# main.net
KiCad netlist of a schematic drawn in EAGLE
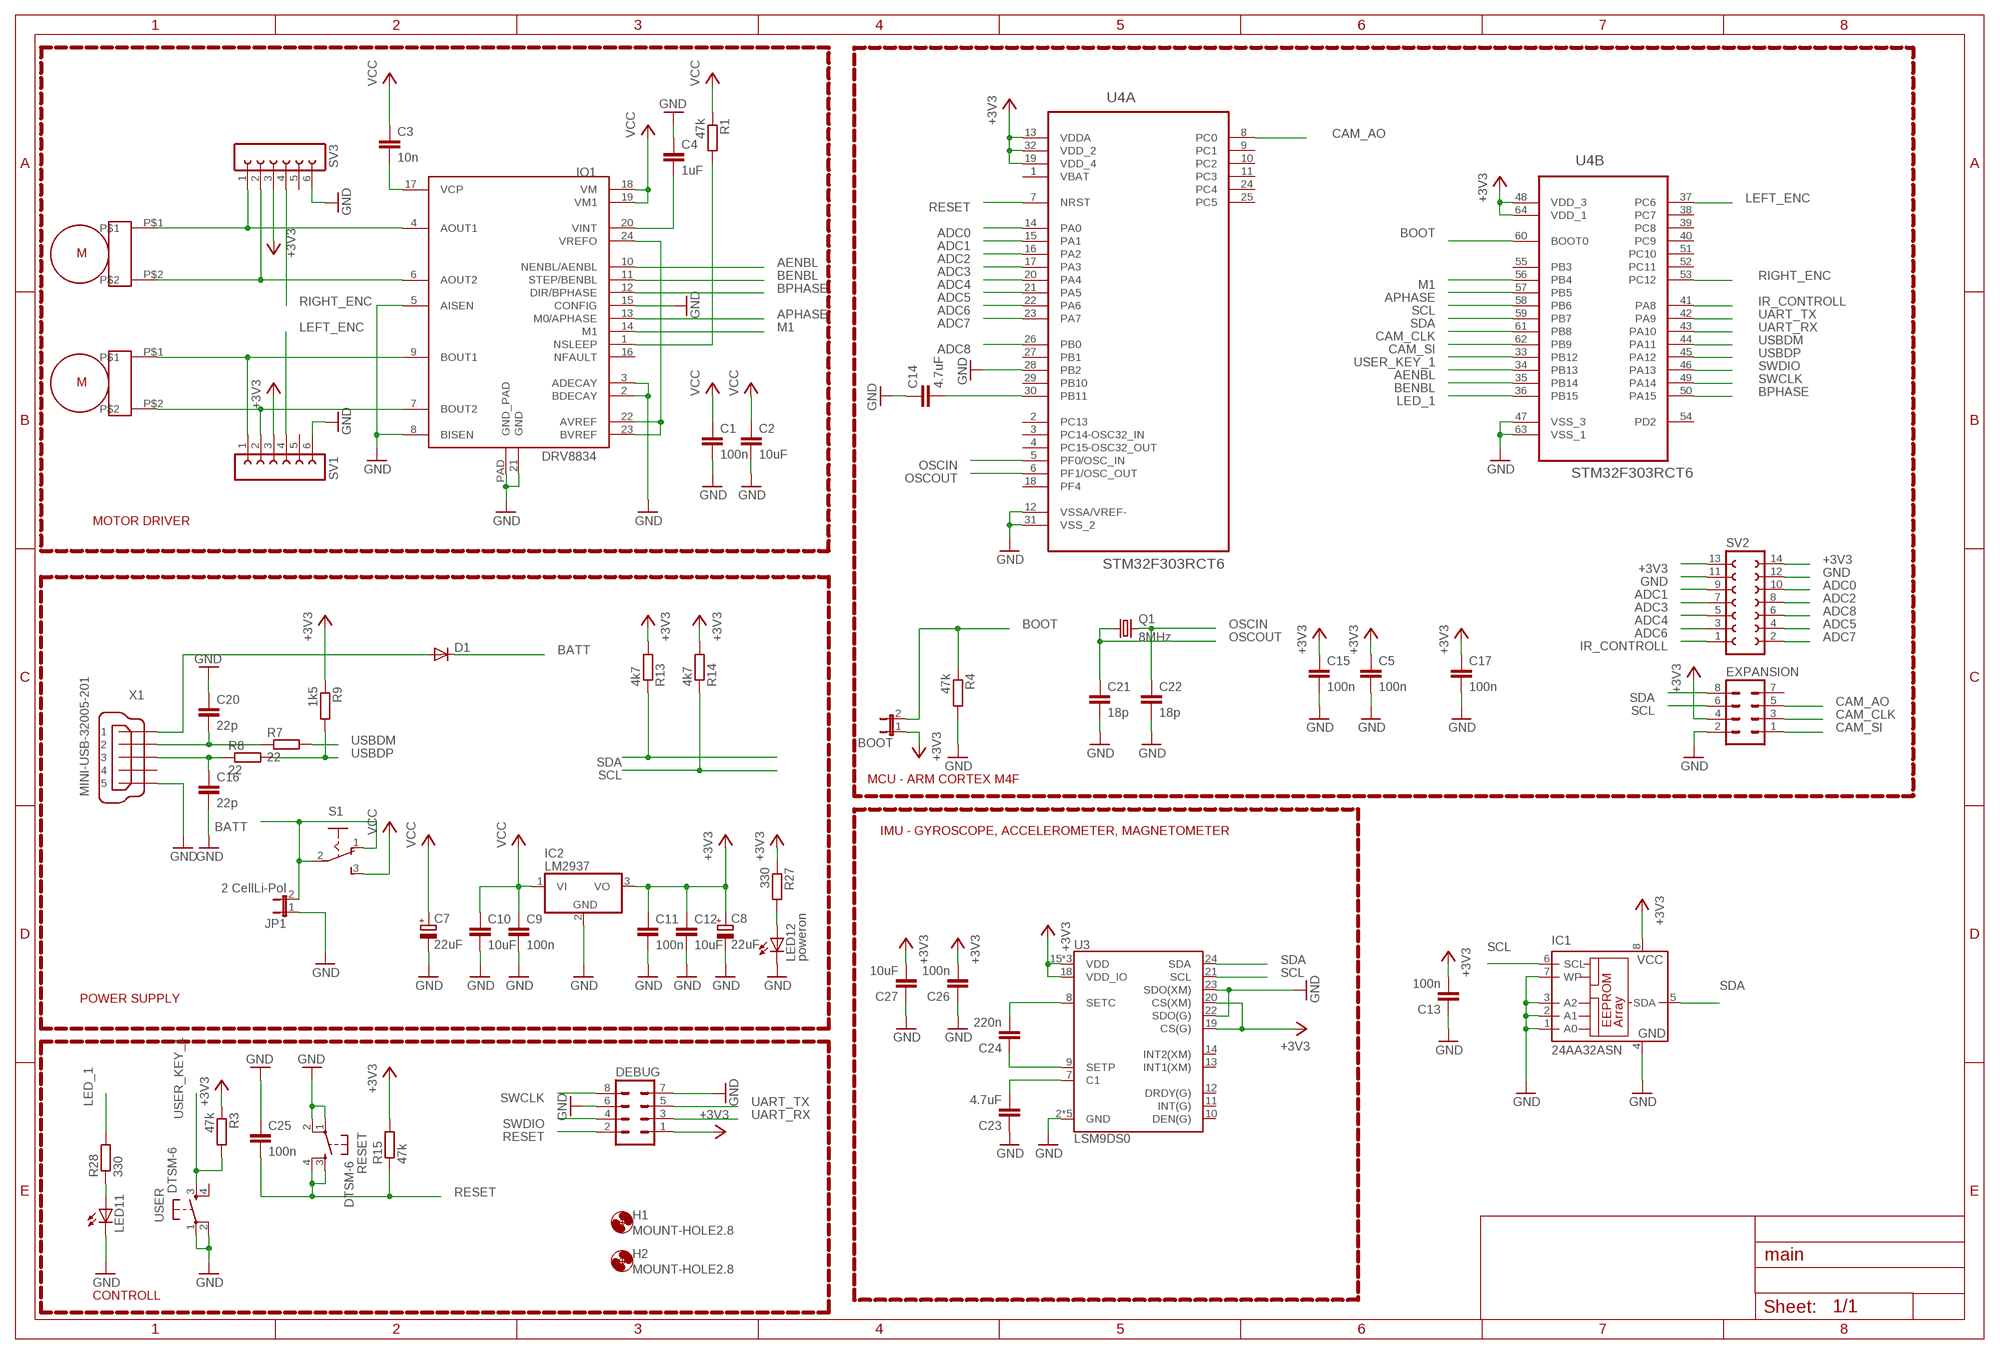
[diagram p0: schematic, sheet 1]

(export (version "E")
  (design (tool "Eeschema 10.0.6"))
  (components
    (comp (ref "BOOT")
      (value "JP1E")
      (footprint "eagle-import:JP1")
      (libsource (lib "eagle-import") (part "JP1E"))
    )
    (comp (ref "C1")
      (value "100n")
      (footprint "eagle-import:C1206")
      (libsource (lib "eagle-import") (part "C-EUC1206"))
    )
    (comp (ref "C2")
      (value "10uF")
      (footprint "eagle-import:C1206")
      (libsource (lib "eagle-import") (part "C-EUC1206"))
    )
    (comp (ref "C3")
      (value "10n")
      (footprint "eagle-import:C1206")
      (libsource (lib "eagle-import") (part "C-EUC1206"))
    )
    (comp (ref "C4")
      (value "1uF")
      (footprint "eagle-import:C1206")
      (libsource (lib "eagle-import") (part "C-EUC1206"))
    )
    (comp (ref "C5")
      (value "100n")
      (footprint "eagle-import:C0805")
      (libsource (lib "eagle-import") (part "C-EUC0805"))
    )
    (comp (ref "C7")
      (value "22uF")
      (footprint "eagle-import:153CLV-0505")
      (libsource (lib "eagle-import") (part "CPOL-EU153CLV-0505"))
    )
    (comp (ref "C8")
      (value "22uF")
      (footprint "eagle-import:153CLV-0505")
      (libsource (lib "eagle-import") (part "CPOL-EU153CLV-0505"))
    )
    (comp (ref "C9")
      (value "100n")
      (footprint "eagle-import:C0805")
      (libsource (lib "eagle-import") (part "C-EUC0805"))
    )
    (comp (ref "C10")
      (value "10uF")
      (footprint "eagle-import:C0805")
      (libsource (lib "eagle-import") (part "C-EUC0805"))
    )
    (comp (ref "C11")
      (value "100n")
      (footprint "eagle-import:C0805")
      (libsource (lib "eagle-import") (part "C-EUC0805"))
    )
    (comp (ref "C12")
      (value "10uF")
      (footprint "eagle-import:C0805")
      (libsource (lib "eagle-import") (part "C-EUC0805"))
    )
    (comp (ref "C13")
      (value "100n")
      (footprint "eagle-import:C0805")
      (libsource (lib "eagle-import") (part "C-EUC0805"))
    )
    (comp (ref "C14")
      (value "4.7uF")
      (footprint "eagle-import:C0805")
      (libsource (lib "eagle-import") (part "C-EUC0805"))
    )
    (comp (ref "C15")
      (value "100n")
      (footprint "eagle-import:C0805")
      (libsource (lib "eagle-import") (part "C-EUC0805"))
    )
    (comp (ref "C16")
      (value "22p")
      (footprint "eagle-import:C0805")
      (libsource (lib "eagle-import") (part "C-EUC0805"))
    )
    (comp (ref "C17")
      (value "100n")
      (footprint "eagle-import:C0805")
      (libsource (lib "eagle-import") (part "C-EUC0805"))
    )
    (comp (ref "C20")
      (value "22p")
      (footprint "eagle-import:C0805")
      (libsource (lib "eagle-import") (part "C-EUC0805"))
    )
    (comp (ref "C21")
      (value "18p")
      (footprint "eagle-import:C0805")
      (libsource (lib "eagle-import") (part "C-EUC0805"))
    )
    (comp (ref "C22")
      (value "18p")
      (footprint "eagle-import:C0805")
      (libsource (lib "eagle-import") (part "C-EUC0805"))
    )
    (comp (ref "C23")
      (value "4.7uF")
      (footprint "eagle-import:C0805")
      (libsource (lib "eagle-import") (part "C-EUC0805"))
    )
    (comp (ref "C24")
      (value "220n")
      (footprint "eagle-import:C0805")
      (libsource (lib "eagle-import") (part "C-EUC0805"))
    )
    (comp (ref "C25")
      (value "100n")
      (footprint "eagle-import:C0805")
      (libsource (lib "eagle-import") (part "C-EUC0805"))
    )
    (comp (ref "C26")
      (value "100n")
      (footprint "eagle-import:C0805")
      (libsource (lib "eagle-import") (part "C-EUC0805"))
    )
    (comp (ref "C27")
      (value "10uF")
      (footprint "eagle-import:C0805")
      (libsource (lib "eagle-import") (part "C-EUC0805"))
    )
    (comp (ref "D1")
      (value "DIODE-SMB")
      (footprint "eagle-import:SMB")
      (libsource (lib "eagle-import") (part "DIODE-SMB"))
    )
    (comp (ref "DEBUG")
      (value "MA04-2")
      (footprint "eagle-import:MA04-2")
      (libsource (lib "eagle-import") (part "MA04-2"))
    )
    (comp (ref "EXPANSION")
      (value "MA04-2")
      (footprint "eagle-import:MA04-2")
      (libsource (lib "eagle-import") (part "MA04-2"))
    )
    (comp (ref "H1")
      (value "MOUNT-HOLE2.8")
      (footprint "eagle-import:2,8")
      (libsource (lib "eagle-import") (part "MOUNT-HOLE2.8"))
    )
    (comp (ref "H2")
      (value "MOUNT-HOLE2.8")
      (footprint "eagle-import:2,8")
      (libsource (lib "eagle-import") (part "MOUNT-HOLE2.8"))
    )
    (comp (ref "IC1")
      (value "24AA32ASN")
      (footprint "eagle-import:SO-08")
      (fields (field (name "MF") "MICROCHIP") (field (name "MPN") "24AA32A-I/SN"))
      (libsource (lib "eagle-import") (part "24SNAA32A"))
    )
    (comp (ref "IC2")
      (value "LM2937")
      (footprint "eagle-import:TO263-3")
      (libsource (lib "eagle-import") (part "LM2937"))
    )
    (comp (ref "IO1")
      (value "DRV8834")
      (footprint "eagle-import:DRV8834_PCK")
      (libsource (lib "eagle-import") (part "DRV8834"))
    )
    (comp (ref "JP1")
      (value "2 CellLi-Pol")
      (footprint "eagle-import:JP1")
      (libsource (lib "eagle-import") (part "JP1E"))
    )
    (comp (ref "LED11")
      (value "LEDCHIPLED_1206")
      (footprint "eagle-import:CHIPLED_1206")
      (libsource (lib "eagle-import") (part "LEDCHIPLED_1206"))
    )
    (comp (ref "LED12")
      (value "poweron")
      (footprint "eagle-import:CHIPLED_1206")
      (libsource (lib "eagle-import") (part "LEDCHIPLED_1206"))
    )
    (comp (ref "Q1")
      (value "8MHz")
      (footprint "eagle-import:CTS406")
      (libsource (lib "eagle-import") (part "CRYSTALCTS406"))
    )
    (comp (ref "R1")
      (value "47k")
      (footprint "eagle-import:M1206")
      (libsource (lib "eagle-import") (part "R-EU_M1206"))
    )
    (comp (ref "R3")
      (value "47k")
      (footprint "eagle-import:M0805")
      (libsource (lib "eagle-import") (part "R-EU_M0805"))
    )
    (comp (ref "R4")
      (value "47k")
      (footprint "eagle-import:M0805")
      (libsource (lib "eagle-import") (part "R-EU_M0805"))
    )
    (comp (ref "R7")
      (value "22")
      (footprint "eagle-import:M0805")
      (libsource (lib "eagle-import") (part "R-EU_M0805"))
    )
    (comp (ref "R8")
      (value "22")
      (footprint "eagle-import:M0805")
      (libsource (lib "eagle-import") (part "R-EU_M0805"))
    )
    (comp (ref "R9")
      (value "1k5")
      (footprint "eagle-import:M0805")
      (libsource (lib "eagle-import") (part "R-EU_M0805"))
    )
    (comp (ref "R13")
      (value "4k7")
      (footprint "eagle-import:M0805")
      (libsource (lib "eagle-import") (part "R-EU_M0805"))
    )
    (comp (ref "R14")
      (value "4k7")
      (footprint "eagle-import:M0805")
      (libsource (lib "eagle-import") (part "R-EU_M0805"))
    )
    (comp (ref "R15")
      (value "47k")
      (footprint "eagle-import:M0805")
      (libsource (lib "eagle-import") (part "R-EU_M0805"))
    )
    (comp (ref "R27")
      (value "330")
      (footprint "eagle-import:M0805")
      (libsource (lib "eagle-import") (part "R-EU_M0805"))
    )
    (comp (ref "R28")
      (value "330")
      (footprint "eagle-import:M0805")
      (libsource (lib "eagle-import") (part "R-EU_M0805"))
    )
    (comp (ref "RESET")
      (value "DTSM-6")
      (footprint "eagle-import:DTSM-6")
      (libsource (lib "eagle-import") (part "DTSM-6"))
    )
    (comp (ref "S1")
      (value "255SB")
      (footprint "eagle-import:255SB")
      (libsource (lib "eagle-import") (part "255SB"))
    )
    (comp (ref "SV1")
      (value "FE06-1")
      (footprint "eagle-import:FE06")
      (libsource (lib "eagle-import") (part "FE06-1"))
    )
    (comp (ref "SV2")
      (value "FE07-2")
      (footprint "eagle-import:FE07-2")
      (libsource (lib "eagle-import") (part "FE07-2"))
    )
    (comp (ref "SV3")
      (value "FE06-1")
      (footprint "eagle-import:FE06")
      (libsource (lib "eagle-import") (part "FE06-1"))
    )
    (comp (ref "U$1")
      (value "MICRO_METAL_GEAR_MOTOR")
      (footprint "eagle-import:MICRO_METAL_GEAR_MOTOR")
      (libsource (lib "eagle-import") (part "MICRO_METAL_GEAR_MOTOR"))
    )
    (comp (ref "U$2")
      (value "MICRO_METAL_GEAR_MOTOR")
      (footprint "eagle-import:MICRO_METAL_GEAR_MOTOR")
      (libsource (lib "eagle-import") (part "MICRO_METAL_GEAR_MOTOR"))
    )
    (comp (ref "U3")
      (value "LSM9DS0")
      (footprint "eagle-import:LGA-24")
      (libsource (lib "eagle-import") (part "LSM9DS0"))
    )
    (comp (ref "U4")
      (value "STM32F303RCT6")
      (footprint "eagle-import:QFP50P1200X1200X160-64N")
      (libsource (lib "eagle-import") (part "STM32F303RCT6"))
    )
    (comp (ref "USER")
      (value "DTSM-6")
      (footprint "eagle-import:DTSM-6")
      (libsource (lib "eagle-import") (part "DTSM-6"))
    )
    (comp (ref "X1")
      (value "MINI-USB-32005-201")
      (footprint "eagle-import:32005-201")
      (libsource (lib "eagle-import") (part "MINI-USB-32005-201"))
    )
  )
  (nets
    (net (code "1") (name "+3V3") (class "Default")
      (node (ref "BOOT") (pin "1") (pinfunction "1_1") (pintype "passive"))
      (node (ref "C11") (pin "1") (pinfunction "1_1") (pintype "passive"))
      (node (ref "C12") (pin "1") (pinfunction "1_1") (pintype "passive"))
      (node (ref "C13") (pin "2") (pinfunction "2_2") (pintype "passive"))
      (node (ref "C15") (pin "1") (pinfunction "1_1") (pintype "passive"))
      (node (ref "C17") (pin "1") (pinfunction "1_1") (pintype "passive"))
      (node (ref "C26") (pin "2") (pinfunction "2_2") (pintype "passive"))
      (node (ref "C27") (pin "2") (pinfunction "2_2") (pintype "passive"))
      (node (ref "C5") (pin "1") (pinfunction "1_1") (pintype "passive"))
      (node (ref "C8") (pin "+") (pinfunction "+_+") (pintype "passive"))
      (node (ref "DEBUG") (pin "1") (pinfunction "1_1") (pintype "passive"))
      (node (ref "EXPANSION") (pin "4") (pinfunction "4_4") (pintype "passive"))
      (node (ref "IC1") (pin "8") (pinfunction "VCC_8") (pintype "power_in"))
      (node (ref "IC2") (pin "3") (pinfunction "VO_3") (pintype "passive"))
      (node (ref "R13") (pin "2") (pinfunction "2_2") (pintype "passive"))
      (node (ref "R14") (pin "2") (pinfunction "2_2") (pintype "passive"))
      (node (ref "R15") (pin "2") (pinfunction "2_2") (pintype "passive"))
      (node (ref "R27") (pin "1") (pinfunction "1_1") (pintype "passive"))
      (node (ref "R3") (pin "1") (pinfunction "1_1") (pintype "passive"))
      (node (ref "R9") (pin "1") (pinfunction "1_1") (pintype "passive"))
      (node (ref "SV1") (pin "3") (pinfunction "3_3") (pintype "passive"))
      (node (ref "SV2") (pin "13") (pinfunction "13_13") (pintype "passive"))
      (node (ref "SV2") (pin "14") (pinfunction "14_14") (pintype "passive"))
      (node (ref "SV3") (pin "3") (pinfunction "3_3") (pintype "passive"))
      (node (ref "U3") (pin "15") (pinfunction "VDD_15") (pintype "bidirectional"))
      (node (ref "U3") (pin "16") (pinfunction "VDD_16") (pintype "bidirectional"))
      (node (ref "U3") (pin "17") (pinfunction "VDD_17") (pintype "bidirectional"))
      (node (ref "U3") (pin "18") (pinfunction "VDD_IO_18") (pintype "bidirectional"))
      (node (ref "U3") (pin "19") (pinfunction "CS(G)_19") (pintype "bidirectional"))
      (node (ref "U3") (pin "20") (pinfunction "CS(XM)_20") (pintype "bidirectional"))
      (node (ref "U4") (pin "13") (pinfunction "VDDA_13") (pintype "power_in"))
      (node (ref "U4") (pin "19") (pinfunction "VDD_4_19") (pintype "power_in"))
      (node (ref "U4") (pin "32") (pinfunction "VDD_2_32") (pintype "power_in"))
      (node (ref "U4") (pin "48") (pinfunction "VDD_3_48") (pintype "power_in"))
      (node (ref "U4") (pin "64") (pinfunction "VDD_1_64") (pintype "power_in"))
    )
    (net (code "2") (name "/ADC0") (class "Default")
      (node (ref "SV2") (pin "10") (pinfunction "10_10") (pintype "passive"))
      (node (ref "U4") (pin "14") (pinfunction "PA0_14") (pintype "bidirectional"))
    )
    (net (code "3") (name "/ADC1") (class "Default")
      (node (ref "SV2") (pin "9") (pinfunction "9_9") (pintype "passive"))
      (node (ref "U4") (pin "15") (pinfunction "PA1_15") (pintype "bidirectional"))
    )
    (net (code "4") (name "/ADC2") (class "Default")
      (node (ref "SV2") (pin "8") (pinfunction "8_8") (pintype "passive"))
      (node (ref "U4") (pin "16") (pinfunction "PA2_16") (pintype "bidirectional"))
    )
    (net (code "5") (name "/ADC3") (class "Default")
      (node (ref "SV2") (pin "7") (pinfunction "7_7") (pintype "passive"))
      (node (ref "U4") (pin "17") (pinfunction "PA3_17") (pintype "bidirectional"))
    )
    (net (code "6") (name "/ADC4") (class "Default")
      (node (ref "SV2") (pin "5") (pinfunction "5_5") (pintype "passive"))
      (node (ref "U4") (pin "20") (pinfunction "PA4_20") (pintype "bidirectional"))
    )
    (net (code "7") (name "/ADC5") (class "Default")
      (node (ref "SV2") (pin "4") (pinfunction "4_4") (pintype "passive"))
      (node (ref "U4") (pin "21") (pinfunction "PA5_21") (pintype "bidirectional"))
    )
    (net (code "8") (name "/ADC6") (class "Default")
      (node (ref "SV2") (pin "3") (pinfunction "3_3") (pintype "passive"))
      (node (ref "U4") (pin "22") (pinfunction "PA6_22") (pintype "bidirectional"))
    )
    (net (code "9") (name "/ADC7") (class "Default")
      (node (ref "SV2") (pin "2") (pinfunction "2_2") (pintype "passive"))
      (node (ref "U4") (pin "23") (pinfunction "PA7_23") (pintype "bidirectional"))
    )
    (net (code "10") (name "/ADC8") (class "Default")
      (node (ref "SV2") (pin "6") (pinfunction "6_6") (pintype "passive"))
      (node (ref "U4") (pin "26") (pinfunction "PB0_26") (pintype "bidirectional"))
    )
    (net (code "11") (name "/AENBL") (class "Default")
      (node (ref "IO1") (pin "10") (pinfunction "NENBL/AENBL_10") (pintype "bidirectional"))
      (node (ref "U4") (pin "34") (pinfunction "PB13_34") (pintype "bidirectional"))
    )
    (net (code "12") (name "/APHASE") (class "Default")
      (node (ref "IO1") (pin "13") (pinfunction "M0/APHASE_13") (pintype "bidirectional"))
      (node (ref "U4") (pin "57") (pinfunction "PB5_57") (pintype "bidirectional"))
    )
    (net (code "13") (name "/BATT") (class "Default")
      (node (ref "D1") (pin "C") (pinfunction "C_C") (pintype "passive"))
      (node (ref "JP1") (pin "2") (pinfunction "2_2") (pintype "passive"))
      (node (ref "S1") (pin "1") (pinfunction "O_1") (pintype "passive"))
      (node (ref "S1") (pin "2") (pinfunction "P_2") (pintype "passive"))
    )
    (net (code "14") (name "/BENBL") (class "Default")
      (node (ref "IO1") (pin "11") (pinfunction "STEP/BENBL_11") (pintype "bidirectional"))
      (node (ref "U4") (pin "35") (pinfunction "PB14_35") (pintype "bidirectional"))
    )
    (net (code "15") (name "/BOOT") (class "Default")
      (node (ref "BOOT") (pin "2") (pinfunction "2_2") (pintype "passive"))
      (node (ref "R4") (pin "1") (pinfunction "1_1") (pintype "passive"))
      (node (ref "U4") (pin "60") (pinfunction "BOOT0_60") (pintype "input"))
    )
    (net (code "16") (name "/BPHASE") (class "Default")
      (node (ref "IO1") (pin "12") (pinfunction "DIR/BPHASE_12") (pintype "bidirectional"))
      (node (ref "U4") (pin "50") (pinfunction "PA15_50") (pintype "bidirectional"))
    )
    (net (code "17") (name "/CAM_AO") (class "Default")
      (node (ref "EXPANSION") (pin "5") (pinfunction "5_5") (pintype "passive"))
      (node (ref "U4") (pin "8") (pinfunction "PC0_8") (pintype "bidirectional"))
    )
    (net (code "18") (name "/CAM_CLK") (class "Default")
      (node (ref "EXPANSION") (pin "3") (pinfunction "3_3") (pintype "passive"))
      (node (ref "U4") (pin "61") (pinfunction "PB8_61") (pintype "bidirectional"))
    )
    (net (code "19") (name "/CAM_SI") (class "Default")
      (node (ref "EXPANSION") (pin "1") (pinfunction "1_1") (pintype "passive"))
      (node (ref "U4") (pin "62") (pinfunction "PB9_62") (pintype "bidirectional"))
    )
    (net (code "20") (name "/IR_CONTROLL") (class "Default")
      (node (ref "SV2") (pin "1") (pinfunction "1_1") (pintype "passive"))
      (node (ref "U4") (pin "41") (pinfunction "PA8_41") (pintype "bidirectional"))
    )
    (net (code "21") (name "/LED_1") (class "Default")
      (node (ref "R28") (pin "2") (pinfunction "2_2") (pintype "passive"))
      (node (ref "U4") (pin "36") (pinfunction "PB15_36") (pintype "bidirectional"))
    )
    (net (code "22") (name "/LEFT_ENC") (class "Default")
      (node (ref "SV1") (pin "4") (pinfunction "4_4") (pintype "passive"))
      (node (ref "U4") (pin "37") (pinfunction "PC6_37") (pintype "bidirectional"))
    )
    (net (code "23") (name "/M1") (class "Default")
      (node (ref "IO1") (pin "14") (pinfunction "M1_14") (pintype "bidirectional"))
      (node (ref "U4") (pin "56") (pinfunction "PB4_56") (pintype "bidirectional"))
    )
    (net (code "24") (name "/OSCIN") (class "Default")
      (node (ref "C22") (pin "1") (pinfunction "1_1") (pintype "passive"))
      (node (ref "Q1") (pin "3") (pinfunction "2_3") (pintype "passive"))
      (node (ref "U4") (pin "5") (pinfunction "PF0/OSC_IN_5") (pintype "bidirectional"))
    )
    (net (code "25") (name "/OSCOUT") (class "Default")
      (node (ref "C21") (pin "1") (pinfunction "1_1") (pintype "passive"))
      (node (ref "Q1") (pin "1") (pinfunction "1_1") (pintype "passive"))
      (node (ref "U4") (pin "6") (pinfunction "PF1/OSC_OUT_6") (pintype "bidirectional"))
    )
    (net (code "26") (name "/RESET") (class "Default")
      (node (ref "C25") (pin "2") (pinfunction "2_2") (pintype "passive"))
      (node (ref "DEBUG") (pin "2") (pinfunction "2_2") (pintype "passive"))
      (node (ref "R15") (pin "1") (pinfunction "1_1") (pintype "passive"))
      (node (ref "RESET") (pin "3") (pinfunction "3_3") (pintype "passive"))
      (node (ref "RESET") (pin "4") (pinfunction "4_4") (pintype "passive"))
      (node (ref "U4") (pin "7") (pinfunction "NRST_7") (pintype "bidirectional"))
    )
    (net (code "27") (name "/RIGHT_ENC") (class "Default")
      (node (ref "SV3") (pin "4") (pinfunction "4_4") (pintype "passive"))
      (node (ref "U4") (pin "53") (pinfunction "PC12_53") (pintype "bidirectional"))
    )
    (net (code "28") (name "/SCL") (class "Default")
      (node (ref "EXPANSION") (pin "6") (pinfunction "6_6") (pintype "passive"))
      (node (ref "IC1") (pin "6") (pinfunction "SCL_6") (pintype "input"))
      (node (ref "R14") (pin "1") (pinfunction "1_1") (pintype "passive"))
      (node (ref "U3") (pin "21") (pinfunction "SCL_21") (pintype "bidirectional"))
      (node (ref "U4") (pin "58") (pinfunction "PB6_58") (pintype "bidirectional"))
    )
    (net (code "29") (name "/SDA") (class "Default")
      (node (ref "EXPANSION") (pin "8") (pinfunction "8_8") (pintype "passive"))
      (node (ref "IC1") (pin "5") (pinfunction "SDA_5") (pintype "bidirectional"))
      (node (ref "R13") (pin "1") (pinfunction "1_1") (pintype "passive"))
      (node (ref "U3") (pin "24") (pinfunction "SDA_24") (pintype "bidirectional"))
      (node (ref "U4") (pin "59") (pinfunction "PB7_59") (pintype "bidirectional"))
    )
    (net (code "30") (name "/SWCLK") (class "Default")
      (node (ref "DEBUG") (pin "8") (pinfunction "8_8") (pintype "passive"))
      (node (ref "U4") (pin "49") (pinfunction "PA14_49") (pintype "bidirectional"))
    )
    (net (code "31") (name "/SWDIO") (class "Default")
      (node (ref "DEBUG") (pin "4") (pinfunction "4_4") (pintype "passive"))
      (node (ref "U4") (pin "46") (pinfunction "PA13_46") (pintype "bidirectional"))
    )
    (net (code "32") (name "/UART_RX") (class "Default")
      (node (ref "DEBUG") (pin "3") (pinfunction "3_3") (pintype "passive"))
      (node (ref "U4") (pin "43") (pinfunction "PA10_43") (pintype "bidirectional"))
    )
    (net (code "33") (name "/UART_TX") (class "Default")
      (node (ref "DEBUG") (pin "5") (pinfunction "5_5") (pintype "passive"))
      (node (ref "U4") (pin "42") (pinfunction "PA9_42") (pintype "bidirectional"))
    )
    (net (code "34") (name "/USBDM") (class "Default")
      (node (ref "R7") (pin "2") (pinfunction "2_2") (pintype "passive"))
      (node (ref "U4") (pin "44") (pinfunction "PA11_44") (pintype "bidirectional"))
    )
    (net (code "35") (name "/USBDP") (class "Default")
      (node (ref "R8") (pin "2") (pinfunction "2_2") (pintype "passive"))
      (node (ref "R9") (pin "2") (pinfunction "2_2") (pintype "passive"))
      (node (ref "U4") (pin "45") (pinfunction "PA12_45") (pintype "bidirectional"))
    )
    (net (code "36") (name "/USER_KEY_1") (class "Default")
      (node (ref "R3") (pin "2") (pinfunction "2_2") (pintype "passive"))
      (node (ref "U4") (pin "33") (pinfunction "PB12_33") (pintype "bidirectional"))
      (node (ref "USER") (pin "3") (pinfunction "3_3") (pintype "passive"))
    )
    (net (code "37") (name "/VBAT") (class "Default")
      (node (ref "U4") (pin "1") (pinfunction "VBAT_1") (pintype "power_in"))
    )
    (net (code "38") (name "GND") (class "Default")
      (node (ref "C1") (pin "2") (pinfunction "2_2") (pintype "passive"))
      (node (ref "C10") (pin "2") (pinfunction "2_2") (pintype "passive"))
      (node (ref "C11") (pin "2") (pinfunction "2_2") (pintype "passive"))
      (node (ref "C12") (pin "2") (pinfunction "2_2") (pintype "passive"))
      (node (ref "C13") (pin "1") (pinfunction "1_1") (pintype "passive"))
      (node (ref "C14") (pin "1") (pinfunction "1_1") (pintype "passive"))
      (node (ref "C15") (pin "2") (pinfunction "2_2") (pintype "passive"))
      (node (ref "C16") (pin "2") (pinfunction "2_2") (pintype "passive"))
      (node (ref "C17") (pin "2") (pinfunction "2_2") (pintype "passive"))
      (node (ref "C2") (pin "2") (pinfunction "2_2") (pintype "passive"))
      (node (ref "C20") (pin "1") (pinfunction "1_1") (pintype "passive"))
      (node (ref "C21") (pin "2") (pinfunction "2_2") (pintype "passive"))
      (node (ref "C22") (pin "2") (pinfunction "2_2") (pintype "passive"))
      (node (ref "C23") (pin "1") (pinfunction "1_1") (pintype "passive"))
      (node (ref "C25") (pin "1") (pinfunction "1_1") (pintype "passive"))
      (node (ref "C26") (pin "1") (pinfunction "1_1") (pintype "passive"))
      (node (ref "C27") (pin "1") (pinfunction "1_1") (pintype "passive"))
      (node (ref "C4") (pin "1") (pinfunction "1_1") (pintype "passive"))
      (node (ref "C5") (pin "2") (pinfunction "2_2") (pintype "passive"))
      (node (ref "C7") (pin "-") (pinfunction "-_-") (pintype "passive"))
      (node (ref "C8") (pin "-") (pinfunction "-_-") (pintype "passive"))
      (node (ref "C9") (pin "2") (pinfunction "2_2") (pintype "passive"))
      (node (ref "DEBUG") (pin "6") (pinfunction "6_6") (pintype "passive"))
      (node (ref "DEBUG") (pin "7") (pinfunction "7_7") (pintype "passive"))
      (node (ref "EXPANSION") (pin "2") (pinfunction "2_2") (pintype "passive"))
      (node (ref "IC1") (pin "1") (pinfunction "A0_1") (pintype "input"))
      (node (ref "IC1") (pin "2") (pinfunction "A1_2") (pintype "input"))
      (node (ref "IC1") (pin "3") (pinfunction "A2_3") (pintype "input"))
      (node (ref "IC1") (pin "4") (pinfunction "GND_4") (pintype "power_in"))
      (node (ref "IC1") (pin "7") (pinfunction "WP_7") (pintype "input"))
      (node (ref "IC2") (pin "2") (pinfunction "GND_2") (pintype "passive"))
      (node (ref "IO1") (pin "15") (pinfunction "CONFIG_15") (pintype "bidirectional"))
      (node (ref "IO1") (pin "2") (pinfunction "BDECAY_2") (pintype "bidirectional"))
      (node (ref "IO1") (pin "21") (pinfunction "GND_21") (pintype "bidirectional"))
      (node (ref "IO1") (pin "3") (pinfunction "ADECAY_3") (pintype "bidirectional"))
      (node (ref "IO1") (pin "5") (pinfunction "AISEN_5") (pintype "bidirectional"))
      (node (ref "IO1") (pin "8") (pinfunction "BISEN_8") (pintype "bidirectional"))
      (node (ref "IO1") (pin "PAD") (pinfunction "GND_PAD_PAD") (pintype "bidirectional"))
      (node (ref "JP1") (pin "1") (pinfunction "1_1") (pintype "passive"))
      (node (ref "LED11") (pin "C") (pinfunction "C_C") (pintype "passive"))
      (node (ref "LED12") (pin "C") (pinfunction "C_C") (pintype "passive"))
      (node (ref "R4") (pin "2") (pinfunction "2_2") (pintype "passive"))
      (node (ref "RESET") (pin "1") (pinfunction "1_1") (pintype "passive"))
      (node (ref "RESET") (pin "2") (pinfunction "2_2") (pintype "passive"))
      (node (ref "SV1") (pin "6") (pinfunction "6_6") (pintype "passive"))
      (node (ref "SV2") (pin "11") (pinfunction "11_11") (pintype "passive"))
      (node (ref "SV2") (pin "12") (pinfunction "12_12") (pintype "passive"))
      (node (ref "SV3") (pin "6") (pinfunction "6_6") (pintype "passive"))
      (node (ref "U3") (pin "2") (pinfunction "GND_2") (pintype "bidirectional"))
      (node (ref "U3") (pin "22") (pinfunction "SDO(G)_22") (pintype "bidirectional"))
      (node (ref "U3") (pin "23") (pinfunction "SDO(XM)_23") (pintype "bidirectional"))
      (node (ref "U3") (pin "3") (pinfunction "GND_3") (pintype "bidirectional"))
      (node (ref "U3") (pin "4") (pinfunction "GND_4") (pintype "bidirectional"))
      (node (ref "U3") (pin "5") (pinfunction "GND_5") (pintype "bidirectional"))
      (node (ref "U3") (pin "6") (pinfunction "GND_6") (pintype "bidirectional"))
      (node (ref "U4") (pin "12") (pinfunction "VSSA/VREF-_12") (pintype "power_in"))
      (node (ref "U4") (pin "28") (pinfunction "PB2_28") (pintype "bidirectional"))
      (node (ref "U4") (pin "31") (pinfunction "VSS_2_31") (pintype "passive"))
      (node (ref "U4") (pin "47") (pinfunction "VSS_3_47") (pintype "passive"))
      (node (ref "U4") (pin "63") (pinfunction "VSS_1_63") (pintype "passive"))
      (node (ref "USER") (pin "1") (pinfunction "1_1") (pintype "passive"))
      (node (ref "USER") (pin "2") (pinfunction "2_2") (pintype "passive"))
      (node (ref "X1") (pin "5") (pinfunction "5_5") (pintype "passive"))
    )
    (net (code "39") (name "Net-(C16-Pad1)") (class "Default")
      (node (ref "C16") (pin "1") (pinfunction "1_1") (pintype "passive"))
      (node (ref "R8") (pin "1") (pinfunction "1_1") (pintype "passive"))
      (node (ref "X1") (pin "3") (pinfunction "3_3") (pintype "passive"))
    )
    (net (code "40") (name "Net-(C20-Pad2)") (class "Default")
      (node (ref "C20") (pin "2") (pinfunction "2_2") (pintype "passive"))
      (node (ref "R7") (pin "1") (pinfunction "1_1") (pintype "passive"))
      (node (ref "X1") (pin "2") (pinfunction "2_2") (pintype "passive"))
    )
    (net (code "41") (name "Net-(D1-PadA)") (class "Default")
      (node (ref "D1") (pin "A") (pinfunction "A_A") (pintype "passive"))
      (node (ref "X1") (pin "1") (pinfunction "1_1") (pintype "passive"))
    )
    (net (code "42") (name "Net-(IO1-AOUT1)") (class "Default")
      (node (ref "IO1") (pin "4") (pinfunction "AOUT1_4") (pintype "bidirectional"))
      (node (ref "SV3") (pin "1") (pinfunction "1_1") (pintype "passive"))
      (node (ref "U$1") (pin "P$1") (pinfunction "P$1_P$1") (pintype "bidirectional"))
    )
    (net (code "43") (name "Net-(IO1-AOUT2)") (class "Default")
      (node (ref "IO1") (pin "6") (pinfunction "AOUT2_6") (pintype "bidirectional"))
      (node (ref "SV3") (pin "2") (pinfunction "2_2") (pintype "passive"))
      (node (ref "U$1") (pin "P$2") (pinfunction "P$2_P$2") (pintype "bidirectional"))
    )
    (net (code "44") (name "Net-(IO1-AVREF)") (class "Default")
      (node (ref "IO1") (pin "22") (pinfunction "AVREF_22") (pintype "bidirectional"))
      (node (ref "IO1") (pin "23") (pinfunction "BVREF_23") (pintype "bidirectional"))
      (node (ref "IO1") (pin "24") (pinfunction "VREFO_24") (pintype "bidirectional"))
    )
    (net (code "45") (name "Net-(IO1-BOUT1)") (class "Default")
      (node (ref "IO1") (pin "9") (pinfunction "BOUT1_9") (pintype "bidirectional"))
      (node (ref "SV1") (pin "1") (pinfunction "1_1") (pintype "passive"))
      (node (ref "U$2") (pin "P$1") (pinfunction "P$1_P$1") (pintype "bidirectional"))
    )
    (net (code "46") (name "Net-(IO1-BOUT2)") (class "Default")
      (node (ref "IO1") (pin "7") (pinfunction "BOUT2_7") (pintype "bidirectional"))
      (node (ref "SV1") (pin "2") (pinfunction "2_2") (pintype "passive"))
      (node (ref "U$2") (pin "P$2") (pinfunction "P$2_P$2") (pintype "bidirectional"))
    )
    (net (code "47") (name "Net-(IO1-NSLEEP)") (class "Default")
      (node (ref "IO1") (pin "1") (pinfunction "NSLEEP_1") (pintype "bidirectional"))
      (node (ref "R1") (pin "2") (pinfunction "2_2") (pintype "passive"))
    )
    (net (code "48") (name "Net-(IO1-VCP)") (class "Default")
      (node (ref "C3") (pin "2") (pinfunction "2_2") (pintype "passive"))
      (node (ref "IO1") (pin "17") (pinfunction "VCP_17") (pintype "bidirectional"))
    )
    (net (code "49") (name "Net-(IO1-VINT)") (class "Default")
      (node (ref "C4") (pin "2") (pinfunction "2_2") (pintype "passive"))
      (node (ref "IO1") (pin "20") (pinfunction "VINT_20") (pintype "bidirectional"))
    )
    (net (code "50") (name "Net-(LED11-PadA)") (class "Default")
      (node (ref "LED11") (pin "A") (pinfunction "A_A") (pintype "passive"))
      (node (ref "R28") (pin "1") (pinfunction "1_1") (pintype "passive"))
    )
    (net (code "51") (name "Net-(LED12-PadA)") (class "Default")
      (node (ref "LED12") (pin "A") (pinfunction "A_A") (pintype "passive"))
      (node (ref "R27") (pin "2") (pinfunction "2_2") (pintype "passive"))
    )
    (net (code "52") (name "Net-(U3-C1)") (class "Default")
      (node (ref "C23") (pin "2") (pinfunction "2_2") (pintype "passive"))
      (node (ref "U3") (pin "7") (pinfunction "C1_7") (pintype "bidirectional"))
    )
    (net (code "53") (name "Net-(U3-SETC)") (class "Default")
      (node (ref "C24") (pin "2") (pinfunction "2_2") (pintype "passive"))
      (node (ref "U3") (pin "8") (pinfunction "SETC_8") (pintype "bidirectional"))
    )
    (net (code "54") (name "Net-(U3-SETP)") (class "Default")
      (node (ref "C24") (pin "1") (pinfunction "1_1") (pintype "passive"))
      (node (ref "U3") (pin "9") (pinfunction "SETP_9") (pintype "bidirectional"))
    )
    (net (code "55") (name "Net-(U4A-PB11)") (class "Default")
      (node (ref "C14") (pin "2") (pinfunction "2_2") (pintype "passive"))
      (node (ref "U4") (pin "30") (pinfunction "PB11_30") (pintype "bidirectional"))
    )
    (net (code "56") (name "VCC") (class "Default")
      (node (ref "C1") (pin "1") (pinfunction "1_1") (pintype "passive"))
      (node (ref "C10") (pin "1") (pinfunction "1_1") (pintype "passive"))
      (node (ref "C2") (pin "1") (pinfunction "1_1") (pintype "passive"))
      (node (ref "C3") (pin "1") (pinfunction "1_1") (pintype "passive"))
      (node (ref "C7") (pin "+") (pinfunction "+_+") (pintype "passive"))
      (node (ref "C9") (pin "1") (pinfunction "1_1") (pintype "passive"))
      (node (ref "IC2") (pin "1") (pinfunction "VI_1") (pintype "input"))
      (node (ref "IO1") (pin "18") (pinfunction "VM_18") (pintype "bidirectional"))
      (node (ref "IO1") (pin "19") (pinfunction "VM1_19") (pintype "bidirectional"))
      (node (ref "R1") (pin "1") (pinfunction "1_1") (pintype "passive"))
      (node (ref "S1") (pin "3") (pinfunction "S_3") (pintype "passive"))
    )
    (net (code "57") (name "unconnected-(EXPANSION-Pad7)") (class "Default")
      (node (ref "EXPANSION") (pin "7") (pinfunction "7_7") (pintype "passive"))
    )
    (net (code "58") (name "unconnected-(IO1-NFAULT-Pad16)") (class "Default")
      (node (ref "IO1") (pin "16") (pinfunction "NFAULT_16") (pintype "bidirectional"))
    )
    (net (code "59") (name "unconnected-(SV1-Pad5)") (class "Default")
      (node (ref "SV1") (pin "5") (pinfunction "5_5") (pintype "passive"))
    )
    (net (code "60") (name "unconnected-(SV3-Pad5)") (class "Default")
      (node (ref "SV3") (pin "5") (pinfunction "5_5") (pintype "passive"))
    )
    (net (code "61") (name "unconnected-(U3-DEN(G)-Pad10)") (class "Default")
      (node (ref "U3") (pin "10") (pinfunction "DEN(G)_10") (pintype "bidirectional"))
    )
    (net (code "62") (name "unconnected-(U3-DRDY(G)-Pad12)") (class "Default")
      (node (ref "U3") (pin "12") (pinfunction "DRDY(G)_12") (pintype "bidirectional"))
    )
    (net (code "63") (name "unconnected-(U3-INT(G)-Pad11)") (class "Default")
      (node (ref "U3") (pin "11") (pinfunction "INT(G)_11") (pintype "bidirectional"))
    )
    (net (code "64") (name "unconnected-(U3-INT1(XM)-Pad13)") (class "Default")
      (node (ref "U3") (pin "13") (pinfunction "INT1(XM)_13") (pintype "bidirectional"))
    )
    (net (code "65") (name "unconnected-(U3-INT2(XM)-Pad14)") (class "Default")
      (node (ref "U3") (pin "14") (pinfunction "INT2(XM)_14") (pintype "bidirectional"))
    )
    (net (code "66") (name "unconnected-(U4A-PB1-Pad27)") (class "Default")
      (node (ref "U4") (pin "27") (pinfunction "PB1_27") (pintype "bidirectional"))
    )
    (net (code "67") (name "unconnected-(U4A-PB10-Pad29)") (class "Default")
      (node (ref "U4") (pin "29") (pinfunction "PB10_29") (pintype "bidirectional"))
    )
    (net (code "68") (name "unconnected-(U4A-PC1-Pad9)") (class "Default")
      (node (ref "U4") (pin "9") (pinfunction "PC1_9") (pintype "bidirectional"))
    )
    (net (code "69") (name "unconnected-(U4A-PC2-Pad10)") (class "Default")
      (node (ref "U4") (pin "10") (pinfunction "PC2_10") (pintype "bidirectional"))
    )
    (net (code "70") (name "unconnected-(U4A-PC3-Pad11)") (class "Default")
      (node (ref "U4") (pin "11") (pinfunction "PC3_11") (pintype "bidirectional"))
    )
    (net (code "71") (name "unconnected-(U4A-PC4-Pad24)") (class "Default")
      (node (ref "U4") (pin "24") (pinfunction "PC4_24") (pintype "bidirectional"))
    )
    (net (code "72") (name "unconnected-(U4A-PC5-Pad25)") (class "Default")
      (node (ref "U4") (pin "25") (pinfunction "PC5_25") (pintype "bidirectional"))
    )
    (net (code "73") (name "unconnected-(U4A-PC13-Pad2)") (class "Default")
      (node (ref "U4") (pin "2") (pinfunction "PC13_2") (pintype "bidirectional"))
    )
    (net (code "74") (name "unconnected-(U4A-PC14-OSC32_IN-Pad3)") (class "Default")
      (node (ref "U4") (pin "3") (pinfunction "PC14-OSC32_IN_3") (pintype "bidirectional"))
    )
    (net (code "75") (name "unconnected-(U4A-PC15-OSC32_OUT-Pad4)") (class "Default")
      (node (ref "U4") (pin "4") (pinfunction "PC15-OSC32_OUT_4") (pintype "bidirectional"))
    )
    (net (code "76") (name "unconnected-(U4A-PF4-Pad18)") (class "Default")
      (node (ref "U4") (pin "18") (pinfunction "PF4_18") (pintype "bidirectional"))
    )
    (net (code "77") (name "unconnected-(U4B-PB3-Pad55)") (class "Default")
      (node (ref "U4") (pin "55") (pinfunction "PB3_55") (pintype "bidirectional"))
    )
    (net (code "78") (name "unconnected-(U4B-PC7-Pad38)") (class "Default")
      (node (ref "U4") (pin "38") (pinfunction "PC7_38") (pintype "bidirectional"))
    )
    (net (code "79") (name "unconnected-(U4B-PC8-Pad39)") (class "Default")
      (node (ref "U4") (pin "39") (pinfunction "PC8_39") (pintype "bidirectional"))
    )
    (net (code "80") (name "unconnected-(U4B-PC9-Pad40)") (class "Default")
      (node (ref "U4") (pin "40") (pinfunction "PC9_40") (pintype "bidirectional"))
    )
    (net (code "81") (name "unconnected-(U4B-PC10-Pad51)") (class "Default")
      (node (ref "U4") (pin "51") (pinfunction "PC10_51") (pintype "bidirectional"))
    )
    (net (code "82") (name "unconnected-(U4B-PC11-Pad52)") (class "Default")
      (node (ref "U4") (pin "52") (pinfunction "PC11_52") (pintype "bidirectional"))
    )
    (net (code "83") (name "unconnected-(U4B-PD2-Pad54)") (class "Default")
      (node (ref "U4") (pin "54") (pinfunction "PD2_54") (pintype "bidirectional"))
    )
    (net (code "84") (name "unconnected-(USER-Pad4)") (class "Default")
      (node (ref "USER") (pin "4") (pinfunction "4_4") (pintype "passive"))
    )
    (net (code "85") (name "unconnected-(X1-Pad4)") (class "Default")
      (node (ref "X1") (pin "4") (pinfunction "4_4") (pintype "passive"))
    )
  )
)
